# 16-BitSW.net
KiCad netlist of a schematic drawn in Altium Designer
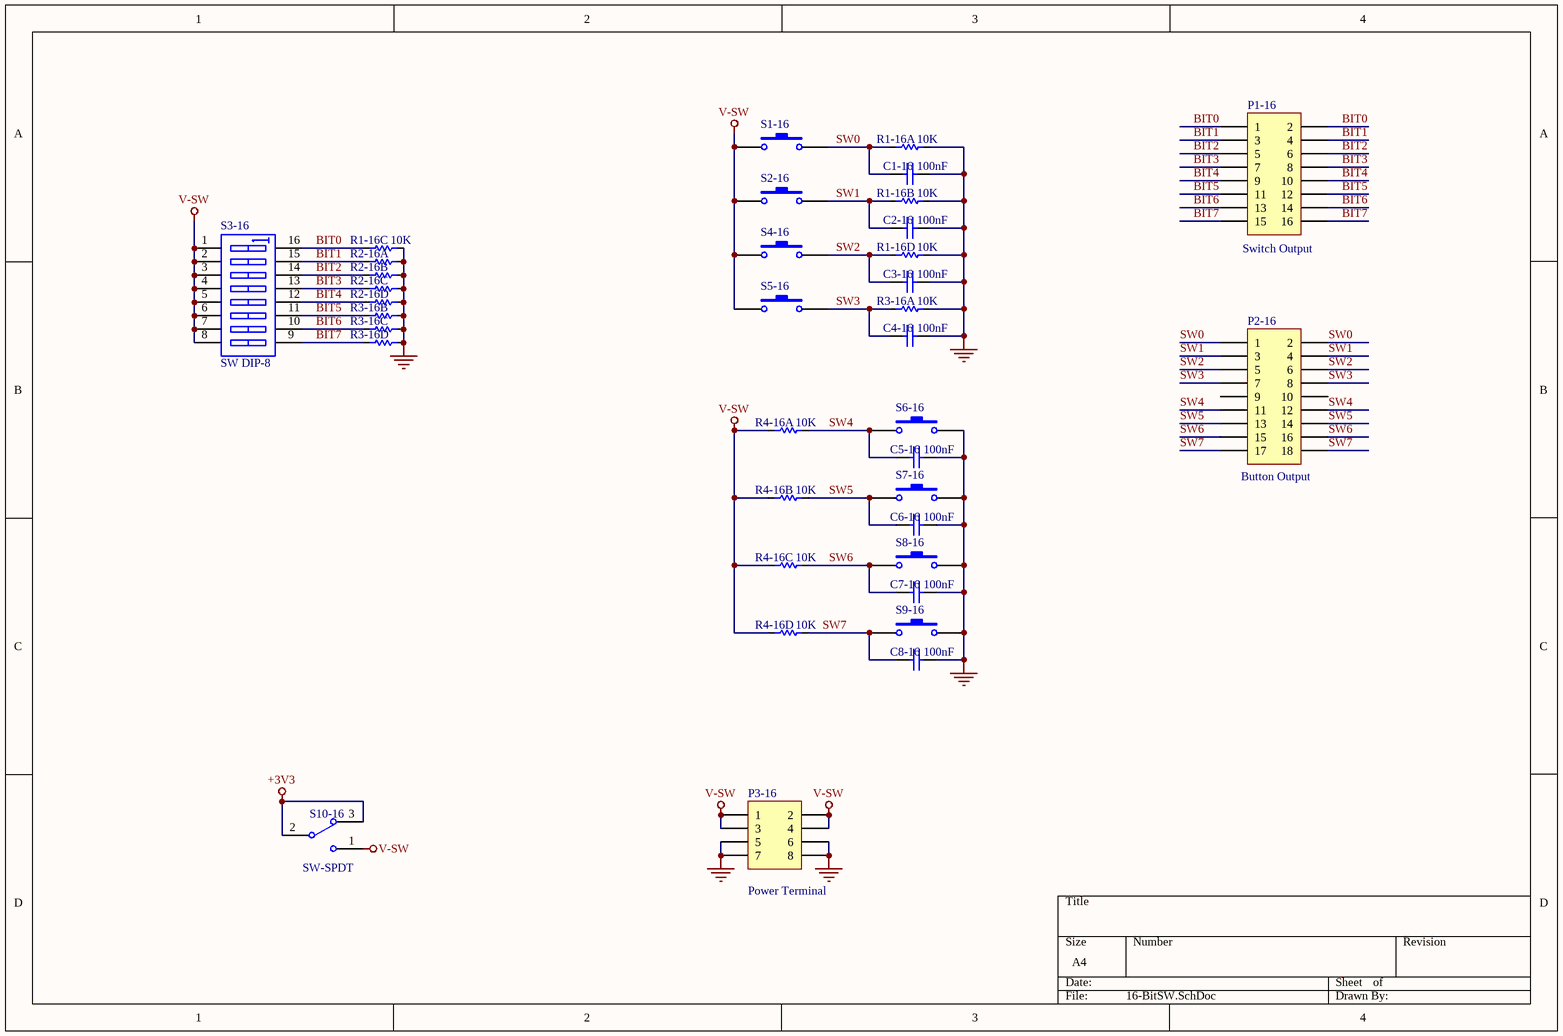
[diagram p0: 16-BitSW.SchDoc]

(export (version "E")
  (design (tool "Eeschema 10.0.6"))
  (components
    (comp (ref "C1-16")
      (value "100nF")
      (footprint "c-0805")
      (description "Capacitor")
      (fields
        (field (name "MANUFACTURER") "Generic Components")
        (field (name "Comment") "104")
        (field (name "PUBLISHER") "Altium Hobart Technology Centre")
      )
      (libsource (lib "Miscellaneous Devices") (part "Cap"))
    )
    (comp (ref "C2-16")
      (value "100nF")
      (footprint "c-0805")
      (description "Capacitor")
      (fields
        (field (name "MANUFACTURER") "Generic Components")
        (field (name "Comment") "104")
        (field (name "PUBLISHER") "Altium Hobart Technology Centre")
      )
      (libsource (lib "Miscellaneous Devices") (part "Cap"))
    )
    (comp (ref "C3-16")
      (value "100nF")
      (footprint "c-0805")
      (description "Capacitor")
      (fields
        (field (name "MANUFACTURER") "Generic Components")
        (field (name "Comment") "104")
        (field (name "PUBLISHER") "Altium Hobart Technology Centre")
      )
      (libsource (lib "Miscellaneous Devices") (part "Cap"))
    )
    (comp (ref "C4-16")
      (value "100nF")
      (footprint "c-0805")
      (description "Capacitor")
      (fields
        (field (name "MANUFACTURER") "Generic Components")
        (field (name "Comment") "104")
        (field (name "PUBLISHER") "Altium Hobart Technology Centre")
      )
      (libsource (lib "Miscellaneous Devices") (part "Cap"))
    )
    (comp (ref "C5-16")
      (value "100nF")
      (footprint "c-0805")
      (description "Capacitor")
      (fields
        (field (name "MANUFACTURER") "Generic Components")
        (field (name "Comment") "104")
        (field (name "PUBLISHER") "Altium Hobart Technology Centre")
      )
      (libsource (lib "Miscellaneous Devices") (part "Cap"))
    )
    (comp (ref "C6-16")
      (value "100nF")
      (footprint "c-0805")
      (description "Capacitor")
      (fields
        (field (name "MANUFACTURER") "Generic Components")
        (field (name "Comment") "104")
        (field (name "PUBLISHER") "Altium Hobart Technology Centre")
      )
      (libsource (lib "Miscellaneous Devices") (part "Cap"))
    )
    (comp (ref "C7-16")
      (value "100nF")
      (footprint "c-0805")
      (description "Capacitor")
      (fields
        (field (name "MANUFACTURER") "Generic Components")
        (field (name "Comment") "104")
        (field (name "PUBLISHER") "Altium Hobart Technology Centre")
      )
      (libsource (lib "Miscellaneous Devices") (part "Cap"))
    )
    (comp (ref "C8-16")
      (value "100nF")
      (footprint "c-0805")
      (description "Capacitor")
      (fields
        (field (name "MANUFACTURER") "Generic Components")
        (field (name "Comment") "104")
        (field (name "PUBLISHER") "Altium Hobart Technology Centre")
      )
      (libsource (lib "Miscellaneous Devices") (part "Cap"))
    )
    (comp (ref "P1-16")
      (value "Switch Output")
      (footprint "JP2.54-F-2x08A")
      (description "Header, 8-Pin, Dual row")
      (fields (field (name "Comment") "Header 8X2"))
      (libsource (lib "Miscellaneous Connectors") (part "Header 8X2"))
    )
    (comp (ref "P2-16")
      (value "Button Output")
      (footprint "JP2.54-F-2x09A")
      (description "Header, 9-Pin, Dual row")
      (fields (field (name "Comment") "Header 9X2"))
      (libsource (lib "Miscellaneous Connectors") (part "Header 9X2"))
    )
    (comp (ref "P3-16")
      (value "Header 4X2")
      (footprint "JP2.54-F-2x04A")
      (description "Header, 4-Pin, Dual row")
      (fields (field (name "PUBLISHER") "Power Terminal"))
      (libsource (lib "Miscellaneous Connectors") (part "Header 4X2"))
    )
    (comp (ref "R1-16")
      (value "10K")
      (footprint "R-Array-0603-4")
      (description "RES ARRAY 4 RES 330 OHM 1206")
      (fields
        (field (name "DIGI-KEY PART NUMBER") "Y9331TR-ND")
        (field (name "MANUFACTURER") "Panasonic Electronic Components")
      )
      (libsource (lib "Dlib") (part "R-8P4R"))
    )
    (comp (ref "R2-16")
      (value "103")
      (footprint "R-Array-0603-4")
      (description "RES ARRAY 4 RES 330 OHM 1206")
      (fields
        (field (name "DIGI-KEY PART NUMBER") "Y9331TR-ND")
        (field (name "MANUFACTURER") "Panasonic Electronic Components")
      )
      (libsource (lib "Dlib") (part "R-8P4R"))
    )
    (comp (ref "R3-16")
      (value "10K")
      (footprint "R-Array-0603-4")
      (description "RES ARRAY 4 RES 330 OHM 1206")
      (fields
        (field (name "DIGI-KEY PART NUMBER") "Y9331TR-ND")
        (field (name "MANUFACTURER") "Panasonic Electronic Components")
      )
      (libsource (lib "Dlib") (part "R-8P4R"))
    )
    (comp (ref "R4-16")
      (value "10K")
      (footprint "R-Array-0603-4")
      (description "RES ARRAY 4 RES 330 OHM 1206")
      (fields
        (field (name "DIGI-KEY PART NUMBER") "Y9331TR-ND")
        (field (name "MANUFACTURER") "Panasonic Electronic Components")
      )
      (libsource (lib "Dlib") (part "R-8P4R"))
    )
    (comp (ref "S1-16")
      (value "SW-S6")
      (footprint "SW-T-S6-SMD")
      (description "Switch")
      (fields (field (name "PUBLISHER") "Altium Limited"))
      (libsource (lib "Miscellaneous Devices") (part "SW-PB"))
    )
    (comp (ref "S2-16")
      (value "SW-S6")
      (footprint "SW-T-S6-SMD")
      (description "Switch")
      (fields (field (name "PUBLISHER") "Altium Limited"))
      (libsource (lib "Miscellaneous Devices") (part "SW-PB"))
    )
    (comp (ref "S3-16")
      (value "SW DIP-8")
      (footprint "SW-DIP8")
      (description "DIP Switch, 8 Position, SPST")
      (fields (field (name "PUBLISHER") "Altium Limited"))
      (libsource (lib "Miscellaneous Devices") (part "SW DIP-8"))
    )
    (comp (ref "S4-16")
      (value "SW-S6")
      (footprint "SW-T-S6-SMD")
      (description "Switch")
      (fields (field (name "PUBLISHER") "Altium Limited"))
      (libsource (lib "Miscellaneous Devices") (part "SW-PB"))
    )
    (comp (ref "S5-16")
      (value "SW-S6")
      (footprint "SW-T-S6-SMD")
      (description "Switch")
      (fields (field (name "PUBLISHER") "Altium Limited"))
      (libsource (lib "Miscellaneous Devices") (part "SW-PB"))
    )
    (comp (ref "S6-16")
      (value "SW-S6")
      (footprint "SW-T-S6-SMD")
      (description "Switch")
      (fields (field (name "PUBLISHER") "Altium Limited"))
      (libsource (lib "Miscellaneous Devices") (part "SW-PB"))
    )
    (comp (ref "S7-16")
      (value "SW-S6")
      (footprint "SW-T-S6-SMD")
      (description "Switch")
      (fields (field (name "PUBLISHER") "Altium Limited"))
      (libsource (lib "Miscellaneous Devices") (part "SW-PB"))
    )
    (comp (ref "S8-16")
      (value "SW-S6")
      (footprint "SW-T-S6-SMD")
      (description "Switch")
      (fields (field (name "PUBLISHER") "Altium Limited"))
      (libsource (lib "Miscellaneous Devices") (part "SW-PB"))
    )
    (comp (ref "S9-16")
      (value "SW-S6")
      (footprint "SW-T-S6-SMD")
      (description "Switch")
      (fields (field (name "PUBLISHER") "Altium Limited"))
      (libsource (lib "Miscellaneous Devices") (part "SW-PB"))
    )
    (comp (ref "S10-16")
      (value "SW-SPDT")
      (footprint "SW-SLIDE-2P-2W")
      (description "SPDT Subminiature Toggle Switch, Right Angle Mounting, Vertical Actuation")
      (fields (field (name "PUBLISHER") "Altium Limited"))
      (libsource (lib "Miscellaneous Devices") (part "SW-SPDT"))
    )
  )
  (nets
    (net (code "1") (name "+3V3") (class "Default")
      (node (ref "S10-16") (pin "2") (pinfunction "2_2") (pintype "passive"))
      (node (ref "S10-16") (pin "3") (pinfunction "3_3") (pintype "passive"))
    )
    (net (code "2") (name "/BIT0") (class "Default")
      (node (ref "P1-16") (pin "1") (pinfunction "1_1") (pintype "passive"))
      (node (ref "P1-16") (pin "2") (pinfunction "2_2") (pintype "passive"))
      (node (ref "R1-16") (pin "5") (pinfunction "1_5") (pintype "passive"))
      (node (ref "S3-16") (pin "16") (pinfunction "B1_16") (pintype "passive"))
    )
    (net (code "3") (name "/BIT1") (class "Default")
      (node (ref "P1-16") (pin "3") (pinfunction "3_3") (pintype "passive"))
      (node (ref "P1-16") (pin "4") (pinfunction "4_4") (pintype "passive"))
      (node (ref "R2-16") (pin "1") (pinfunction "1_1") (pintype "passive"))
      (node (ref "S3-16") (pin "15") (pinfunction "B2_15") (pintype "passive"))
    )
    (net (code "4") (name "/BIT2") (class "Default")
      (node (ref "P1-16") (pin "5") (pinfunction "5_5") (pintype "passive"))
      (node (ref "P1-16") (pin "6") (pinfunction "6_6") (pintype "passive"))
      (node (ref "R2-16") (pin "3") (pinfunction "1_3") (pintype "passive"))
      (node (ref "S3-16") (pin "14") (pinfunction "B3_14") (pintype "passive"))
    )
    (net (code "5") (name "/BIT3") (class "Default")
      (node (ref "P1-16") (pin "7") (pinfunction "7_7") (pintype "passive"))
      (node (ref "P1-16") (pin "8") (pinfunction "8_8") (pintype "passive"))
      (node (ref "R2-16") (pin "5") (pinfunction "1_5") (pintype "passive"))
      (node (ref "S3-16") (pin "13") (pinfunction "B4_13") (pintype "passive"))
    )
    (net (code "6") (name "/BIT4") (class "Default")
      (node (ref "P1-16") (pin "10") (pinfunction "10_10") (pintype "passive"))
      (node (ref "P1-16") (pin "9") (pinfunction "9_9") (pintype "passive"))
      (node (ref "R2-16") (pin "7") (pinfunction "1_7") (pintype "passive"))
      (node (ref "S3-16") (pin "12") (pinfunction "B5_12") (pintype "passive"))
    )
    (net (code "7") (name "/BIT5") (class "Default")
      (node (ref "P1-16") (pin "11") (pinfunction "11_11") (pintype "passive"))
      (node (ref "P1-16") (pin "12") (pinfunction "12_12") (pintype "passive"))
      (node (ref "R3-16") (pin "3") (pinfunction "1_3") (pintype "passive"))
      (node (ref "S3-16") (pin "11") (pinfunction "B6_11") (pintype "passive"))
    )
    (net (code "8") (name "/BIT6") (class "Default")
      (node (ref "P1-16") (pin "13") (pinfunction "13_13") (pintype "passive"))
      (node (ref "P1-16") (pin "14") (pinfunction "14_14") (pintype "passive"))
      (node (ref "R3-16") (pin "5") (pinfunction "1_5") (pintype "passive"))
      (node (ref "S3-16") (pin "10") (pinfunction "B7_10") (pintype "passive"))
    )
    (net (code "9") (name "/BIT7") (class "Default")
      (node (ref "P1-16") (pin "15") (pinfunction "15_15") (pintype "passive"))
      (node (ref "P1-16") (pin "16") (pinfunction "16_16") (pintype "passive"))
      (node (ref "R3-16") (pin "7") (pinfunction "1_7") (pintype "passive"))
      (node (ref "S3-16") (pin "9") (pinfunction "B8_9") (pintype "passive"))
    )
    (net (code "10") (name "/SW0") (class "Default")
      (node (ref "C1-16") (pin "2") (pinfunction "2_2") (pintype "passive"))
      (node (ref "P2-16") (pin "1") (pinfunction "1_1") (pintype "passive"))
      (node (ref "P2-16") (pin "2") (pinfunction "2_2") (pintype "passive"))
      (node (ref "R1-16") (pin "1") (pinfunction "1_1") (pintype "passive"))
      (node (ref "S1-16") (pin "2") (pinfunction "2_2") (pintype "passive"))
    )
    (net (code "11") (name "/SW1") (class "Default")
      (node (ref "C2-16") (pin "2") (pinfunction "2_2") (pintype "passive"))
      (node (ref "P2-16") (pin "3") (pinfunction "3_3") (pintype "passive"))
      (node (ref "P2-16") (pin "4") (pinfunction "4_4") (pintype "passive"))
      (node (ref "R1-16") (pin "3") (pinfunction "1_3") (pintype "passive"))
      (node (ref "S2-16") (pin "2") (pinfunction "2_2") (pintype "passive"))
    )
    (net (code "12") (name "/SW2") (class "Default")
      (node (ref "C3-16") (pin "2") (pinfunction "2_2") (pintype "passive"))
      (node (ref "P2-16") (pin "5") (pinfunction "5_5") (pintype "passive"))
      (node (ref "P2-16") (pin "6") (pinfunction "6_6") (pintype "passive"))
      (node (ref "R1-16") (pin "7") (pinfunction "1_7") (pintype "passive"))
      (node (ref "S4-16") (pin "2") (pinfunction "2_2") (pintype "passive"))
    )
    (net (code "13") (name "/SW3") (class "Default")
      (node (ref "C4-16") (pin "2") (pinfunction "2_2") (pintype "passive"))
      (node (ref "P2-16") (pin "7") (pinfunction "7_7") (pintype "passive"))
      (node (ref "P2-16") (pin "8") (pinfunction "8_8") (pintype "passive"))
      (node (ref "R3-16") (pin "1") (pinfunction "1_1") (pintype "passive"))
      (node (ref "S5-16") (pin "2") (pinfunction "2_2") (pintype "passive"))
    )
    (net (code "14") (name "/SW4") (class "Default")
      (node (ref "C5-16") (pin "2") (pinfunction "2_2") (pintype "passive"))
      (node (ref "P2-16") (pin "11") (pinfunction "11_11") (pintype "passive"))
      (node (ref "P2-16") (pin "12") (pinfunction "12_12") (pintype "passive"))
      (node (ref "R4-16") (pin "2") (pinfunction "2_2") (pintype "passive"))
      (node (ref "S6-16") (pin "1") (pinfunction "1_1") (pintype "passive"))
    )
    (net (code "15") (name "/SW5") (class "Default")
      (node (ref "C6-16") (pin "2") (pinfunction "2_2") (pintype "passive"))
      (node (ref "P2-16") (pin "13") (pinfunction "13_13") (pintype "passive"))
      (node (ref "P2-16") (pin "14") (pinfunction "14_14") (pintype "passive"))
      (node (ref "R4-16") (pin "4") (pinfunction "2_4") (pintype "passive"))
      (node (ref "S7-16") (pin "1") (pinfunction "1_1") (pintype "passive"))
    )
    (net (code "16") (name "/SW6") (class "Default")
      (node (ref "C7-16") (pin "2") (pinfunction "2_2") (pintype "passive"))
      (node (ref "P2-16") (pin "15") (pinfunction "15_15") (pintype "passive"))
      (node (ref "P2-16") (pin "16") (pinfunction "16_16") (pintype "passive"))
      (node (ref "R4-16") (pin "6") (pinfunction "2_6") (pintype "passive"))
      (node (ref "S8-16") (pin "1") (pinfunction "1_1") (pintype "passive"))
    )
    (net (code "17") (name "/SW7") (class "Default")
      (node (ref "C8-16") (pin "2") (pinfunction "2_2") (pintype "passive"))
      (node (ref "P2-16") (pin "17") (pinfunction "17_17") (pintype "passive"))
      (node (ref "P2-16") (pin "18") (pinfunction "18_18") (pintype "passive"))
      (node (ref "R4-16") (pin "8") (pinfunction "2_8") (pintype "passive"))
      (node (ref "S9-16") (pin "1") (pinfunction "1_1") (pintype "passive"))
    )
    (net (code "18") (name "GND") (class "Default")
      (node (ref "C1-16") (pin "1") (pinfunction "1_1") (pintype "passive"))
      (node (ref "C2-16") (pin "1") (pinfunction "1_1") (pintype "passive"))
      (node (ref "C3-16") (pin "1") (pinfunction "1_1") (pintype "passive"))
      (node (ref "C4-16") (pin "1") (pinfunction "1_1") (pintype "passive"))
      (node (ref "C5-16") (pin "1") (pinfunction "1_1") (pintype "passive"))
      (node (ref "C6-16") (pin "1") (pinfunction "1_1") (pintype "passive"))
      (node (ref "C7-16") (pin "1") (pinfunction "1_1") (pintype "passive"))
      (node (ref "C8-16") (pin "1") (pinfunction "1_1") (pintype "passive"))
      (node (ref "P3-16") (pin "5") (pinfunction "5_5") (pintype "passive"))
      (node (ref "P3-16") (pin "6") (pinfunction "6_6") (pintype "passive"))
      (node (ref "P3-16") (pin "7") (pinfunction "7_7") (pintype "passive"))
      (node (ref "P3-16") (pin "8") (pinfunction "8_8") (pintype "passive"))
      (node (ref "R1-16") (pin "2") (pinfunction "2_2") (pintype "passive"))
      (node (ref "R1-16") (pin "4") (pinfunction "2_4") (pintype "passive"))
      (node (ref "R1-16") (pin "6") (pinfunction "2_6") (pintype "passive"))
      (node (ref "R1-16") (pin "8") (pinfunction "2_8") (pintype "passive"))
      (node (ref "R2-16") (pin "2") (pinfunction "2_2") (pintype "passive"))
      (node (ref "R2-16") (pin "4") (pinfunction "2_4") (pintype "passive"))
      (node (ref "R2-16") (pin "6") (pinfunction "2_6") (pintype "passive"))
      (node (ref "R2-16") (pin "8") (pinfunction "2_8") (pintype "passive"))
      (node (ref "R3-16") (pin "2") (pinfunction "2_2") (pintype "passive"))
      (node (ref "R3-16") (pin "4") (pinfunction "2_4") (pintype "passive"))
      (node (ref "R3-16") (pin "6") (pinfunction "2_6") (pintype "passive"))
      (node (ref "R3-16") (pin "8") (pinfunction "2_8") (pintype "passive"))
      (node (ref "S6-16") (pin "2") (pinfunction "2_2") (pintype "passive"))
      (node (ref "S7-16") (pin "2") (pinfunction "2_2") (pintype "passive"))
      (node (ref "S8-16") (pin "2") (pinfunction "2_2") (pintype "passive"))
      (node (ref "S9-16") (pin "2") (pinfunction "2_2") (pintype "passive"))
    )
    (net (code "19") (name "V-SW") (class "Default")
      (node (ref "P3-16") (pin "1") (pinfunction "1_1") (pintype "passive"))
      (node (ref "P3-16") (pin "2") (pinfunction "2_2") (pintype "passive"))
      (node (ref "P3-16") (pin "3") (pinfunction "3_3") (pintype "passive"))
      (node (ref "P3-16") (pin "4") (pinfunction "4_4") (pintype "passive"))
      (node (ref "R4-16") (pin "1") (pinfunction "1_1") (pintype "passive"))
      (node (ref "R4-16") (pin "3") (pinfunction "1_3") (pintype "passive"))
      (node (ref "R4-16") (pin "5") (pinfunction "1_5") (pintype "passive"))
      (node (ref "R4-16") (pin "7") (pinfunction "1_7") (pintype "passive"))
      (node (ref "S1-16") (pin "1") (pinfunction "1_1") (pintype "passive"))
      (node (ref "S10-16") (pin "1") (pinfunction "1_1") (pintype "passive"))
      (node (ref "S2-16") (pin "1") (pinfunction "1_1") (pintype "passive"))
      (node (ref "S3-16") (pin "1") (pinfunction "A1_1") (pintype "passive"))
      (node (ref "S3-16") (pin "2") (pinfunction "A2_2") (pintype "passive"))
      (node (ref "S3-16") (pin "3") (pinfunction "A3_3") (pintype "passive"))
      (node (ref "S3-16") (pin "4") (pinfunction "A4_4") (pintype "passive"))
      (node (ref "S3-16") (pin "5") (pinfunction "A5_5") (pintype "passive"))
      (node (ref "S3-16") (pin "6") (pinfunction "A6_6") (pintype "passive"))
      (node (ref "S3-16") (pin "7") (pinfunction "A7_7") (pintype "passive"))
      (node (ref "S3-16") (pin "8") (pinfunction "A8_8") (pintype "passive"))
      (node (ref "S4-16") (pin "1") (pinfunction "1_1") (pintype "passive"))
      (node (ref "S5-16") (pin "1") (pinfunction "1_1") (pintype "passive"))
    )
    (net (code "20") (name "unconnected-(P2-16-Pad9)") (class "Default")
      (node (ref "P2-16") (pin "9") (pinfunction "9_9") (pintype "passive"))
    )
    (net (code "21") (name "unconnected-(P2-16-Pad10)") (class "Default")
      (node (ref "P2-16") (pin "10") (pinfunction "10_10") (pintype "passive"))
    )
  )
)
